# Schematic.net
KiCad netlist of a schematic drawn in EasyEDA
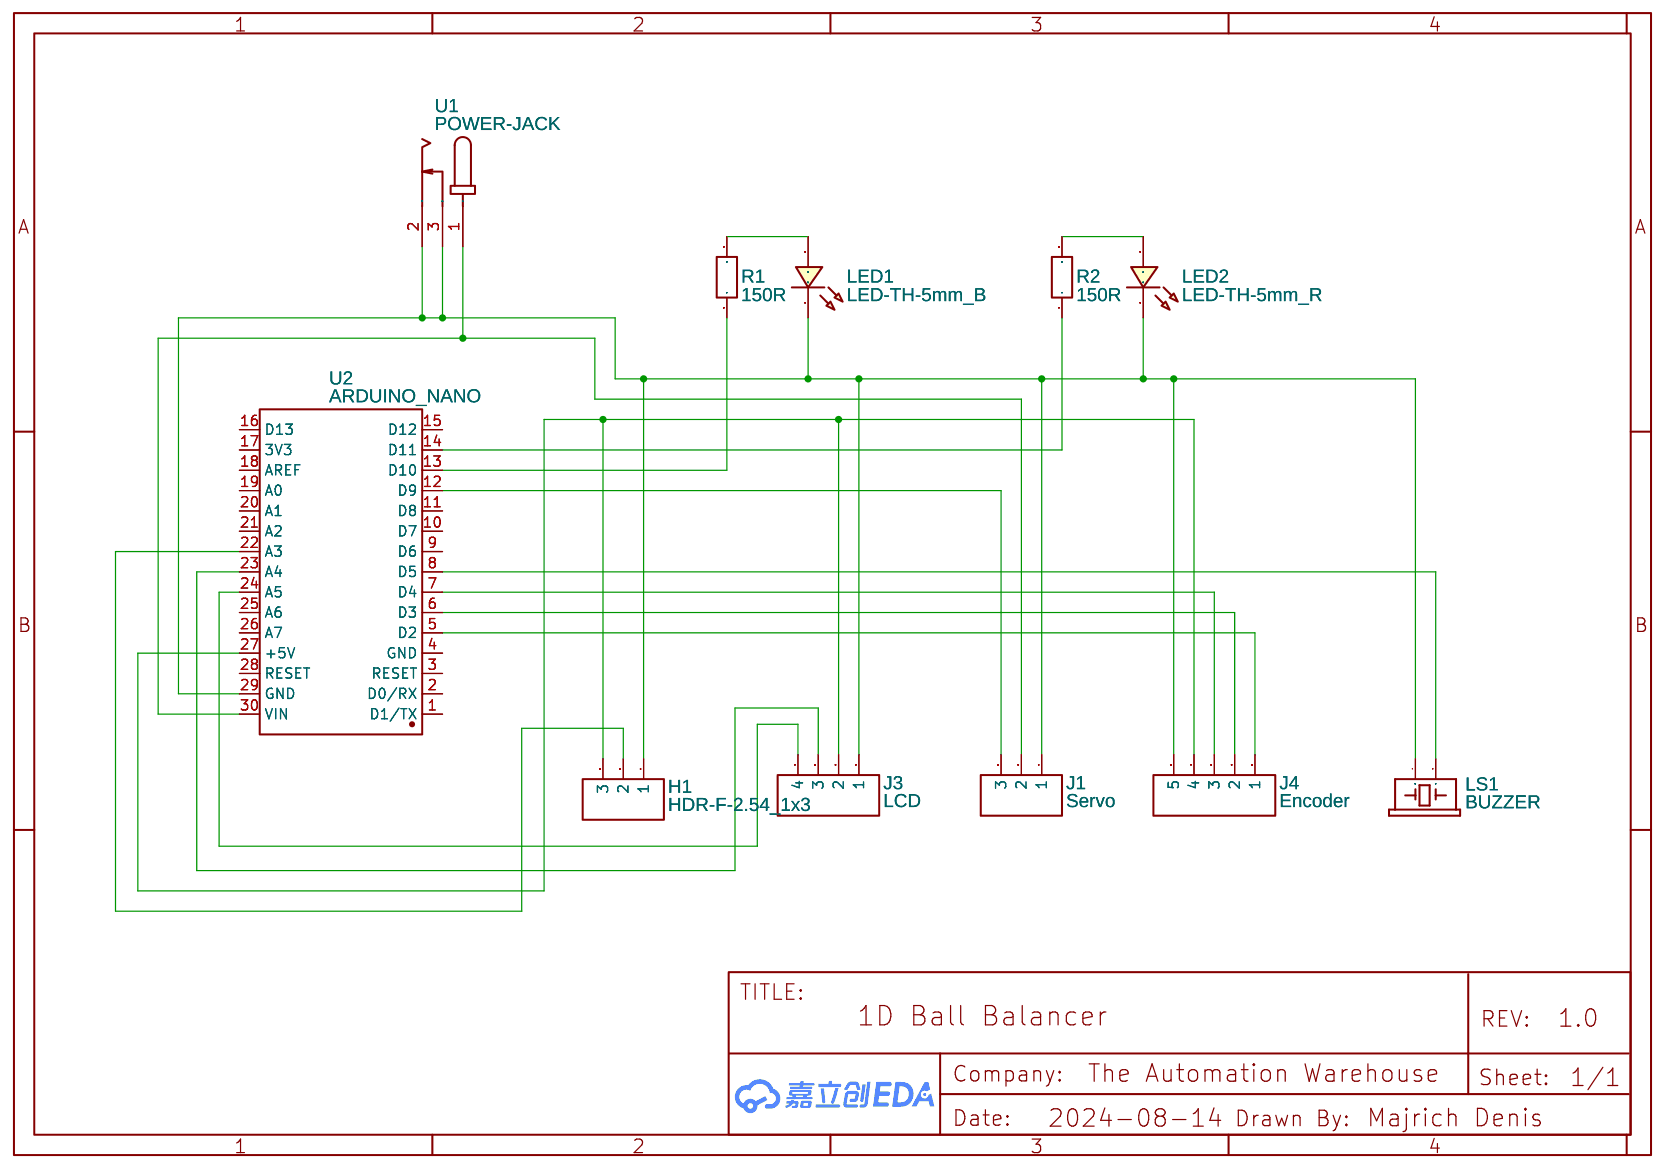
[diagram p0: schematic sheet]

(export (version "E")
  (design (tool "Eeschema 10.0.6"))
  (components
    (comp (ref "H1")
      (value "HDR-F-2.54_1x3")
      (fields (field (name "BOM_Supplier Part") "C146690"))
      (libsource (lib "") (part "HDR-F-2.54_1x3"))
    )
    (comp (ref "J1")
      (value "Servo")
      (fields (field (name "BOM_Supplier Part") "C180248"))
      (libsource (lib "") (part "HDR-M-2.54_1x3"))
    )
    (comp (ref "J3")
      (value "LCD")
      (fields (field (name "BOM_Supplier Part") "C124378"))
      (libsource (lib "") (part "HDR-M-2.54_1x4"))
    )
    (comp (ref "J4")
      (value "Encoder")
      (fields (field (name "BOM_Supplier Part") "C358687"))
      (libsource (lib "") (part "HDR-M-2.54_1x5"))
    )
    (comp (ref "LED1") (value "LED-TH-5mm_B") (libsource (lib "") (part "LED-TH-5mm_B")))
    (comp (ref "LED2")
      (value "LED-TH-5mm_R")
      (fields
        (field (name "BOM_Manufacturer Part") "333-2SURD/S530-A3")
        (field (name "BOM_Supplier Part") "C87271")
      )
      (libsource (lib "") (part "LED-TH-5mm_R"))
    )
    (comp (ref "LS1") (value "BUZZER") (libsource (lib "") (part "BUZZER-PTH_NO_SILK")))
    (comp (ref "R1") (value "150R") (libsource (lib "") (part "R_AXIAL-0.4_EU")))
    (comp (ref "R2") (value "150R") (libsource (lib "") (part "R_AXIAL-0.4_EU")))
    (comp (ref "U1")
      (value "POWER-JACK")
      (fields (field (name "BOM_Supplier Part") "C9900001795"))
      (libsource (lib "") (part "POWER-JACK"))
    )
    (comp (ref "U2") (value "ARDUINO_NANO") (libsource (lib "") (part "ARDUINO_NANO")))
  )
  (nets
    (net (code "1") (name "Net-(LED1-Pad1)") (class "Default")
      (node (ref "LED1") (pin "1") (pinfunction "1_1") (pintype "unspecified"))
      (node (ref "R1") (pin "2") (pinfunction "2_2") (pintype "unspecified"))
    )
    (net (code "2") (name "Net-(LED2-Pad1)") (class "Default")
      (node (ref "LED2") (pin "1") (pinfunction "1_1") (pintype "unspecified"))
      (node (ref "R2") (pin "2") (pinfunction "2_2") (pintype "unspecified"))
    )
    (net (code "3") (name "Net-(LS1-1)") (class "Default")
      (node (ref "LS1") (pin "+") (pinfunction "1_+") (pintype "bidirectional"))
      (node (ref "U2") (pin "8") (pinfunction "D5_8") (pintype "unspecified"))
    )
    (net (code "4") (name "Net-(LS1-2)") (class "Default")
      (node (ref "H1") (pin "1") (pinfunction "1_1") (pintype "input"))
      (node (ref "J1") (pin "1") (pinfunction "1_1") (pintype "input"))
      (node (ref "J3") (pin "1") (pinfunction "1_1") (pintype "unspecified"))
      (node (ref "J4") (pin "5") (pinfunction "5_5") (pintype "unspecified"))
      (node (ref "LED1") (pin "2") (pinfunction "2_2") (pintype "unspecified"))
      (node (ref "LED2") (pin "2") (pinfunction "2_2") (pintype "unspecified"))
      (node (ref "LS1") (pin "-") (pinfunction "2_-") (pintype "bidirectional"))
      (node (ref "U1") (pin "2") (pinfunction "2_2") (pintype "unspecified"))
      (node (ref "U1") (pin "3") (pinfunction "3_3") (pintype "unspecified"))
      (node (ref "U2") (pin "29") (pinfunction "GND_29") (pintype "unspecified"))
    )
    (net (code "5") (name "Net-(U2-+5V)") (class "Default")
      (node (ref "H1") (pin "3") (pinfunction "3_3") (pintype "input"))
      (node (ref "J3") (pin "2") (pinfunction "2_2") (pintype "unspecified"))
      (node (ref "J4") (pin "4") (pinfunction "4_4") (pintype "unspecified"))
      (node (ref "U2") (pin "27") (pinfunction "+5V_27") (pintype "unspecified"))
    )
    (net (code "6") (name "Net-(U2-A3)") (class "Default")
      (node (ref "H1") (pin "2") (pinfunction "2_2") (pintype "input"))
      (node (ref "U2") (pin "22") (pinfunction "A3_22") (pintype "unspecified"))
    )
    (net (code "7") (name "Net-(U2-A4)") (class "Default")
      (node (ref "J3") (pin "3") (pinfunction "3_3") (pintype "unspecified"))
      (node (ref "U2") (pin "23") (pinfunction "A4_23") (pintype "unspecified"))
    )
    (net (code "8") (name "Net-(U2-A5)") (class "Default")
      (node (ref "J3") (pin "4") (pinfunction "4_4") (pintype "unspecified"))
      (node (ref "U2") (pin "24") (pinfunction "A5_24") (pintype "unspecified"))
    )
    (net (code "9") (name "Net-(U2-D2)") (class "Default")
      (node (ref "J4") (pin "1") (pinfunction "1_1") (pintype "unspecified"))
      (node (ref "U2") (pin "5") (pinfunction "D2_5") (pintype "unspecified"))
    )
    (net (code "10") (name "Net-(U2-D3)") (class "Default")
      (node (ref "J4") (pin "2") (pinfunction "2_2") (pintype "unspecified"))
      (node (ref "U2") (pin "6") (pinfunction "D3_6") (pintype "unspecified"))
    )
    (net (code "11") (name "Net-(U2-D4)") (class "Default")
      (node (ref "J4") (pin "3") (pinfunction "3_3") (pintype "unspecified"))
      (node (ref "U2") (pin "7") (pinfunction "D4_7") (pintype "unspecified"))
    )
    (net (code "12") (name "Net-(U2-D9)") (class "Default")
      (node (ref "J1") (pin "3") (pinfunction "3_3") (pintype "input"))
      (node (ref "U2") (pin "12") (pinfunction "D9_12") (pintype "unspecified"))
    )
    (net (code "13") (name "Net-(U2-D10)") (class "Default")
      (node (ref "R1") (pin "1") (pinfunction "1_1") (pintype "unspecified"))
      (node (ref "U2") (pin "13") (pinfunction "D10_13") (pintype "unspecified"))
    )
    (net (code "14") (name "Net-(U2-D11)") (class "Default")
      (node (ref "R2") (pin "1") (pinfunction "1_1") (pintype "unspecified"))
      (node (ref "U2") (pin "14") (pinfunction "D11_14") (pintype "unspecified"))
    )
    (net (code "15") (name "Net-(U2-VIN)") (class "Default")
      (node (ref "J1") (pin "2") (pinfunction "2_2") (pintype "input"))
      (node (ref "U1") (pin "1") (pinfunction "1_1") (pintype "unspecified"))
      (node (ref "U2") (pin "30") (pinfunction "VIN_30") (pintype "unspecified"))
    )
    (net (code "16") (name "unconnected-(U2-3V3-Pad17)") (class "Default")
      (node (ref "U2") (pin "17") (pinfunction "3V3_17") (pintype "unspecified"))
    )
    (net (code "17") (name "unconnected-(U2-A0-Pad19)") (class "Default")
      (node (ref "U2") (pin "19") (pinfunction "A0_19") (pintype "unspecified"))
    )
    (net (code "18") (name "unconnected-(U2-A1-Pad20)") (class "Default")
      (node (ref "U2") (pin "20") (pinfunction "A1_20") (pintype "unspecified"))
    )
    (net (code "19") (name "unconnected-(U2-A2-Pad21)") (class "Default")
      (node (ref "U2") (pin "21") (pinfunction "A2_21") (pintype "unspecified"))
    )
    (net (code "20") (name "unconnected-(U2-A6-Pad25)") (class "Default")
      (node (ref "U2") (pin "25") (pinfunction "A6_25") (pintype "unspecified"))
    )
    (net (code "21") (name "unconnected-(U2-A7-Pad26)") (class "Default")
      (node (ref "U2") (pin "26") (pinfunction "A7_26") (pintype "unspecified"))
    )
    (net (code "22") (name "unconnected-(U2-AREF-Pad18)") (class "Default")
      (node (ref "U2") (pin "18") (pinfunction "AREF_18") (pintype "unspecified"))
    )
    (net (code "23") (name "unconnected-(U2-D0{slash}RX-Pad2)") (class "Default")
      (node (ref "U2") (pin "2") (pinfunction "D0/RX_2") (pintype "unspecified"))
    )
    (net (code "24") (name "unconnected-(U2-D1{slash}TX-Pad1)") (class "Default")
      (node (ref "U2") (pin "1") (pinfunction "D1/TX_1") (pintype "unspecified"))
    )
    (net (code "25") (name "unconnected-(U2-D6-Pad9)") (class "Default")
      (node (ref "U2") (pin "9") (pinfunction "D6_9") (pintype "unspecified"))
    )
    (net (code "26") (name "unconnected-(U2-D7-Pad10)") (class "Default")
      (node (ref "U2") (pin "10") (pinfunction "D7_10") (pintype "unspecified"))
    )
    (net (code "27") (name "unconnected-(U2-D8-Pad11)") (class "Default")
      (node (ref "U2") (pin "11") (pinfunction "D8_11") (pintype "unspecified"))
    )
    (net (code "28") (name "unconnected-(U2-D12-Pad15)") (class "Default")
      (node (ref "U2") (pin "15") (pinfunction "D12_15") (pintype "unspecified"))
    )
    (net (code "29") (name "unconnected-(U2-D13-Pad16)") (class "Default")
      (node (ref "U2") (pin "16") (pinfunction "D13_16") (pintype "unspecified"))
    )
    (net (code "30") (name "unconnected-(U2-GND-Pad4)") (class "Default")
      (node (ref "U2") (pin "4") (pinfunction "GND_4") (pintype "unspecified"))
    )
    (net (code "31") (name "unconnected-(U2-RESET-Pad3)") (class "Default")
      (node (ref "U2") (pin "3") (pinfunction "RESET_3") (pintype "unspecified"))
    )
    (net (code "32") (name "unconnected-(U2-RESET-Pad28)") (class "Default")
      (node (ref "U2") (pin "28") (pinfunction "RESET_28") (pintype "unspecified"))
    )
  )
)
